# oring_circuit.net
KiCad netlist of a schematic drawn in Altium Designer
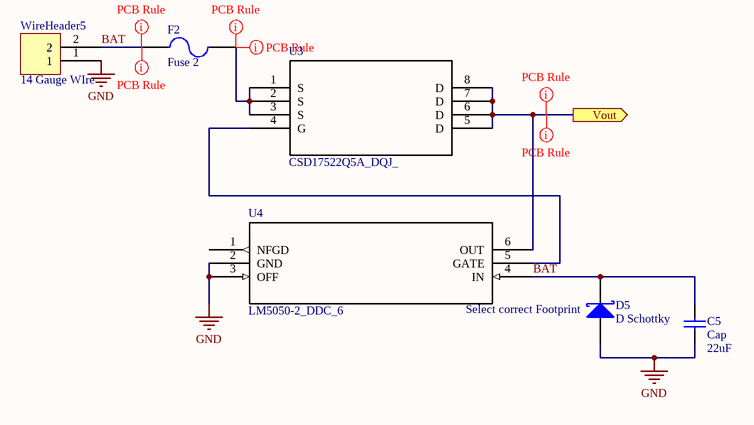
[diagram p0: oring_circuit.SchDoc]

(export (version "E")
  (design (tool "Eeschema 10.0.6"))
  (components
    (comp (ref "C5")
      (value "Cap")
      (footprint "C0805")
      (description "Capacitor")
      (fields (field (name "ALTIUM_VALUE") "22uF") (field (name "PUBLISHER") "Altium Limited"))
      (libsource (lib "Miscellaneous Devices") (part "Cap"))
    )
    (comp (ref "D5")
      (value "D Schottky")
      (footprint "AXIAL-0.3")
      (description "Schottky Diode")
      (fields (field (name "PUBLISHER") "Altium Limited"))
      (libsource (lib "Miscellaneous Devices") (part "D Schottky"))
    )
    (comp (ref "F2")
      (value "Fuse 2")
      (footprint "PIN-W2/E2.8")
      (description "Fuse")
      (fields (field (name "PUBLISHER") "Altium Limited"))
      (libsource (lib "Miscellaneous Devices") (part "Fuse 2"))
    )
    (comp (ref "U3")
      (value "CSD17522Q5A_DQJ_")
      (footprint "DQJ8")
      (description "Imported")
      (fields
        (field (name "MANUFACTURER") "Texas Instruments")
        (field (name "GENERIC_PART_NUMBER") "CSD17522Q5A")
      )
      (libsource (lib "CSD17522Q5A") (part "CSD17522Q5A_DQJ_"))
    )
    (comp (ref "U4")
      (value "LM5050-2_DDC_6")
      (footprint "MK06A")
      (description "Imported")
      (fields
        (field (name "MANUFACTURER") "Texas Instruments")
        (field (name "MANUFACTURER_PART_NUMBER") "lm5050-2_ddc_6")
      )
      (libsource (lib "lm5050-2") (part "LM5050-2_DDC_6"))
    )
    (comp (ref "WireHeader5")
      (value "14 Gauge WIre")
      (footprint "WireHeader")
      (libsource (lib "InvestiGator") (part "WireHeader"))
    )
  )
  (nets
    (net (code "2") (name "/BAT") (class "Default")
      (node (ref "C5") (pin "2") (pinfunction "2_2") (pintype "passive"))
      (node (ref "D5") (pin "2") (pinfunction "K_2") (pintype "passive"))
      (node (ref "F2") (pin "1") (pinfunction "1_1") (pintype "passive"))
      (node (ref "U4") (pin "4") (pinfunction "IN_4") (pintype "input"))
      (node (ref "WireHeader5") (pin "2") (pinfunction "2_2") (pintype "passive"))
    )
    (net (code "3") (name "/Vout") (class "Default")
      (node (ref "U3") (pin "5") (pinfunction "D_5") (pintype "passive"))
      (node (ref "U3") (pin "6") (pinfunction "D_6") (pintype "passive"))
      (node (ref "U3") (pin "7") (pinfunction "D_7") (pintype "passive"))
      (node (ref "U3") (pin "8") (pinfunction "D_8") (pintype "passive"))
      (node (ref "U4") (pin "6") (pinfunction "OUT_6") (pintype "passive"))
    )
    (net (code "4") (name "GND") (class "Default")
      (node (ref "C5") (pin "1") (pinfunction "1_1") (pintype "passive"))
      (node (ref "D5") (pin "1") (pinfunction "A_1") (pintype "passive"))
      (node (ref "U4") (pin "2") (pinfunction "GND_2") (pintype "power_in"))
      (node (ref "U4") (pin "3") (pinfunction "OFF_3") (pintype "input"))
      (node (ref "WireHeader5") (pin "1") (pinfunction "1_1") (pintype "passive"))
    )
    (net (code "5") (name "Net-(F2-Pad2)") (class "Default")
      (node (ref "F2") (pin "2") (pinfunction "2_2") (pintype "passive"))
      (node (ref "U3") (pin "1") (pinfunction "S_1") (pintype "passive"))
      (node (ref "U3") (pin "2") (pinfunction "S_2") (pintype "passive"))
      (node (ref "U3") (pin "3") (pinfunction "S_3") (pintype "passive"))
    )
    (net (code "6") (name "Net-(U3-G)") (class "Default")
      (node (ref "U3") (pin "4") (pinfunction "G_4") (pintype "passive"))
      (node (ref "U4") (pin "5") (pinfunction "GATE_5") (pintype "passive"))
    )
    (net (code "7") (name "unconnected-(U4-NFGD-Pad1)") (class "Default")
      (node (ref "U4") (pin "1") (pinfunction "NFGD_1") (pintype "output"))
    )
  )
)
